# powersupply5v.net
KiCad netlist of a schematic drawn in EAGLE
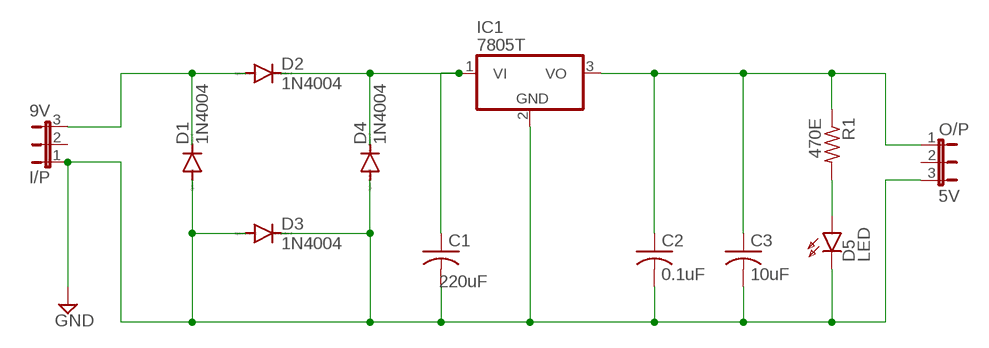
[diagram p0: schematic, sheet 1]

(export (version "E")
  (design (tool "Eeschema 10.0.6"))
  (components
    (comp (ref "C1")
      (value "220uF")
      (footprint "eagle-import:C025-024X044")
      (libsource (lib "eagle-import") (part "C-US025-024X044"))
    )
    (comp (ref "C2")
      (value "0.1uF")
      (footprint "eagle-import:C025-024X044")
      (libsource (lib "eagle-import") (part "C-US025-024X044"))
    )
    (comp (ref "C3")
      (value "10uF")
      (footprint "eagle-import:C025-024X044")
      (libsource (lib "eagle-import") (part "C-US025-024X044"))
    )
    (comp (ref "D1")
      (value "1N4004")
      (footprint "eagle-import:DO41-10")
      (libsource (lib "eagle-import") (part "1N4004"))
    )
    (comp (ref "D2")
      (value "1N4004")
      (footprint "eagle-import:DO41-10")
      (libsource (lib "eagle-import") (part "1N4004"))
    )
    (comp (ref "D3")
      (value "1N4004")
      (footprint "eagle-import:DO41-10")
      (libsource (lib "eagle-import") (part "1N4004"))
    )
    (comp (ref "D4")
      (value "1N4004")
      (footprint "eagle-import:DO41-10")
      (libsource (lib "eagle-import") (part "1N4004"))
    )
    (comp (ref "D5")
      (value "LED")
      (footprint "eagle-import:HLMP6")
      (fields (field (name "MF") "AGILENT TECHNOLOGIES") (field (name "MPN") "HLMP-6500"))
      (libsource (lib "eagle-import") (part "HLMP6"))
    )
    (comp (ref "I/P")
      (value "9V")
      (footprint "eagle-import:JP2W")
      (libsource (lib "eagle-import") (part "JP2W"))
    )
    (comp (ref "IC1")
      (value "7805T")
      (footprint "eagle-import:TO220H")
      (libsource (lib "eagle-import") (part "78T05"))
    )
    (comp (ref "O/P")
      (value "5V")
      (footprint "eagle-import:JP2W")
      (libsource (lib "eagle-import") (part "JP2W"))
    )
    (comp (ref "R1")
      (value "470E")
      (footprint "eagle-import:0204V")
      (libsource (lib "eagle-import") (part "R-US_0204/2V"))
    )
  )
  (nets
    (net (code "1") (name "GND") (class "Default")
      (node (ref "C1") (pin "2") (pinfunction "2_2") (pintype "passive"))
      (node (ref "C2") (pin "2") (pinfunction "2_2") (pintype "passive"))
      (node (ref "C3") (pin "2") (pinfunction "2_2") (pintype "passive"))
      (node (ref "D1") (pin "A") (pinfunction "A_A") (pintype "passive"))
      (node (ref "D3") (pin "A") (pinfunction "A_A") (pintype "passive"))
      (node (ref "D3") (pin "C") (pinfunction "C_C") (pintype "passive"))
      (node (ref "D4") (pin "A") (pinfunction "A_A") (pintype "passive"))
      (node (ref "D5") (pin "K") (pinfunction "K_K") (pintype "passive"))
      (node (ref "I/P") (pin "1") (pinfunction "1_1") (pintype "passive"))
      (node (ref "IC1") (pin "2") (pinfunction "GND_2") (pintype "passive"))
      (node (ref "O/P") (pin "3") (pinfunction "3_3") (pintype "passive"))
    )
    (net (code "2") (name "Net-(D1-PadC)") (class "Default")
      (node (ref "D1") (pin "C") (pinfunction "C_C") (pintype "passive"))
      (node (ref "D2") (pin "A") (pinfunction "A_A") (pintype "passive"))
      (node (ref "I/P") (pin "3") (pinfunction "3_3") (pintype "passive"))
    )
    (net (code "3") (name "Net-(D5-PadA)") (class "Default")
      (node (ref "D5") (pin "A") (pinfunction "A_A") (pintype "passive"))
      (node (ref "R1") (pin "2") (pinfunction "2_2") (pintype "passive"))
    )
    (net (code "4") (name "Net-(IC1-VI)") (class "Default")
      (node (ref "C1") (pin "1") (pinfunction "1_1") (pintype "passive"))
      (node (ref "D2") (pin "C") (pinfunction "C_C") (pintype "passive"))
      (node (ref "D4") (pin "C") (pinfunction "C_C") (pintype "passive"))
      (node (ref "IC1") (pin "1") (pinfunction "VI_1") (pintype "input"))
    )
    (net (code "5") (name "Net-(IC1-VO)") (class "Default")
      (node (ref "C2") (pin "1") (pinfunction "1_1") (pintype "passive"))
      (node (ref "C3") (pin "1") (pinfunction "1_1") (pintype "passive"))
      (node (ref "IC1") (pin "3") (pinfunction "VO_3") (pintype "passive"))
      (node (ref "O/P") (pin "1") (pinfunction "1_1") (pintype "passive"))
      (node (ref "R1") (pin "1") (pinfunction "1_1") (pintype "passive"))
    )
    (net (code "6") (name "unconnected-(I/P-Pad2)") (class "Default")
      (node (ref "I/P") (pin "2") (pinfunction "2_2") (pintype "passive"))
    )
    (net (code "7") (name "unconnected-(O/P-Pad2)") (class "Default")
      (node (ref "O/P") (pin "2") (pinfunction "2_2") (pintype "passive"))
    )
  )
)
